# Fogger_Sheild.net
KiCad netlist of a schematic drawn in EAGLE
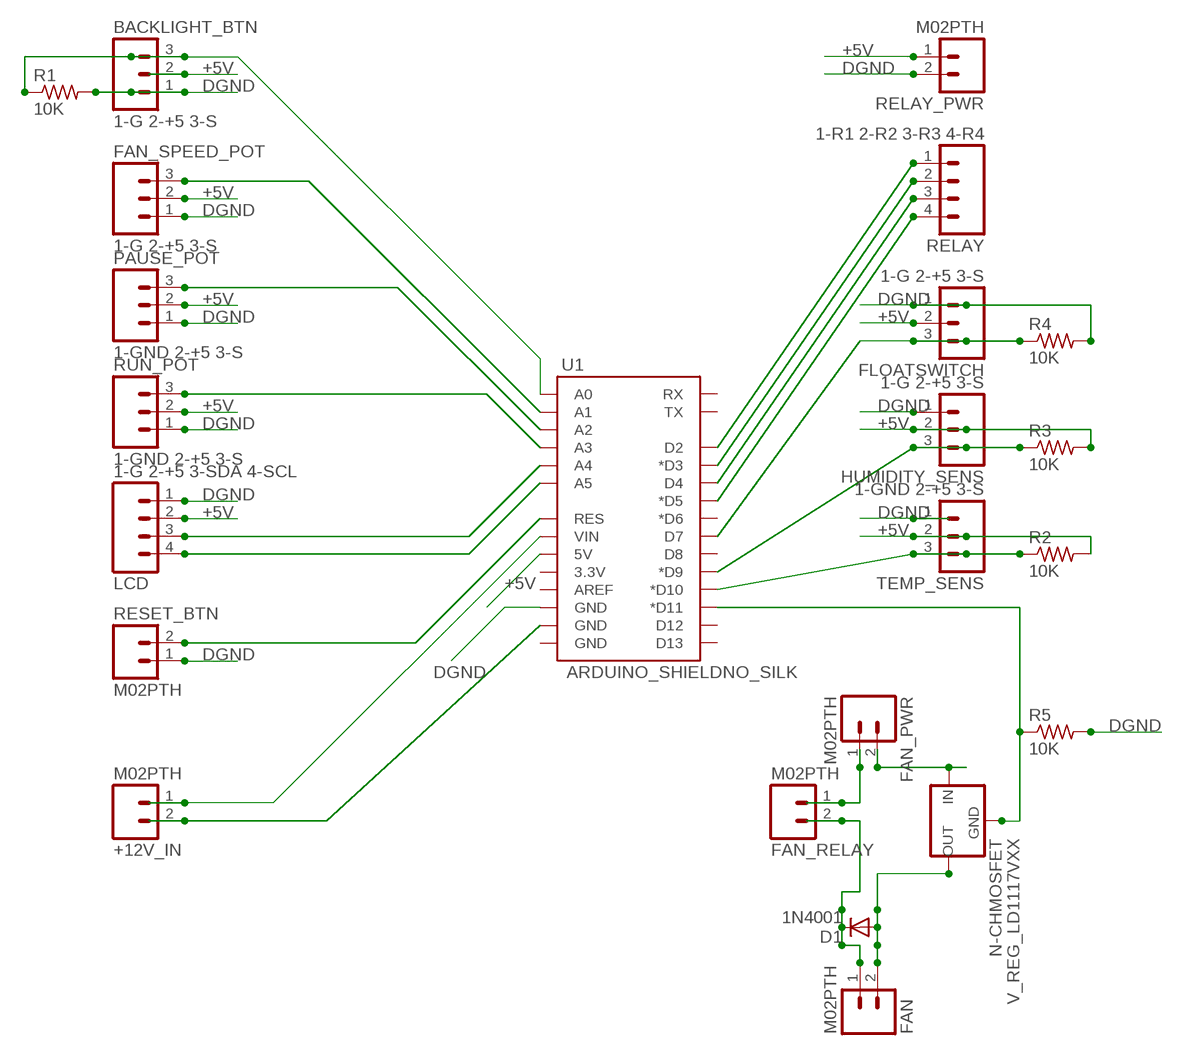
[diagram p0: schematic, sheet 1]

(export (version "E")
  (design (tool "Eeschema 10.0.6"))
  (components
    (comp (ref "+12V_IN")
      (value "M02PTH")
      (footprint "eagle-import:1X02")
      (libsource (lib "eagle-import") (part "M02PTH"))
    )
    (comp (ref "BACKLIGHT_BTN")
      (value "1-G 2-+5 3-S")
      (footprint "eagle-import:1X03_LOCK")
      (libsource (lib "eagle-import") (part "M03LOCK"))
    )
    (comp (ref "D1")
      (value "1N4001")
      (footprint "eagle-import:DIODE-1N4001")
      (libsource (lib "eagle-import") (part "DIODEPTH"))
    )
    (comp (ref "FAN")
      (value "M02PTH")
      (footprint "eagle-import:1X02")
      (libsource (lib "eagle-import") (part "M02PTH"))
    )
    (comp (ref "FAN_PWR")
      (value "M02PTH")
      (footprint "eagle-import:1X02")
      (libsource (lib "eagle-import") (part "M02PTH"))
    )
    (comp (ref "FAN_RELAY")
      (value "M02PTH")
      (footprint "eagle-import:1X02")
      (libsource (lib "eagle-import") (part "M02PTH"))
    )
    (comp (ref "FAN_SPEED_POT")
      (value "1-G 2-+5 3-S")
      (footprint "eagle-import:1X03")
      (libsource (lib "eagle-import") (part "M03PTH"))
    )
    (comp (ref "FLOATSWITCH")
      (value "1-G 2-+5 3-S")
      (footprint "eagle-import:1X03_LOCK")
      (libsource (lib "eagle-import") (part "M03LOCK"))
    )
    (comp (ref "HUMIDITY_SENS")
      (value "1-G 2-+5 3-S")
      (footprint "eagle-import:1X03")
      (libsource (lib "eagle-import") (part "M03PTH"))
    )
    (comp (ref "LCD")
      (value "1-G 2-+5 3-SDA 4-SCL")
      (footprint "eagle-import:1X04")
      (libsource (lib "eagle-import") (part "M04PTH"))
    )
    (comp (ref "N-CHMOSFET")
      (value "V_REG_LD1117VXX")
      (footprint "eagle-import:78XXL")
      (libsource (lib "eagle-import") (part "V_REG_LD1117VXX"))
    )
    (comp (ref "PAUSE_POT")
      (value "1-GND 2-+5 3-S")
      (footprint "eagle-import:1X03_LOCK")
      (libsource (lib "eagle-import") (part "M03LOCK"))
    )
    (comp (ref "R1")
      (value "10K")
      (footprint "eagle-import:0204_5")
      (libsource (lib "eagle-import") (part "R-US_0204/5"))
    )
    (comp (ref "R2")
      (value "10K")
      (footprint "eagle-import:0204V")
      (libsource (lib "eagle-import") (part "R-US_0204/2V"))
    )
    (comp (ref "R3")
      (value "10K")
      (footprint "eagle-import:0204V")
      (libsource (lib "eagle-import") (part "R-US_0204/2V"))
    )
    (comp (ref "R4")
      (value "10K")
      (footprint "eagle-import:0204_5")
      (libsource (lib "eagle-import") (part "R-US_0204/5"))
    )
    (comp (ref "R5")
      (value "10K")
      (footprint "eagle-import:0204V")
      (libsource (lib "eagle-import") (part "R-US_0204/2V"))
    )
    (comp (ref "RELAY")
      (value "1-R1 2-R2 3-R3 4-R4")
      (footprint "eagle-import:1X04")
      (libsource (lib "eagle-import") (part "M04PTH"))
    )
    (comp (ref "RELAY_PWR")
      (value "M02PTH")
      (footprint "eagle-import:1X02")
      (libsource (lib "eagle-import") (part "M02PTH"))
    )
    (comp (ref "RESET_BTN")
      (value "M02PTH")
      (footprint "eagle-import:1X02")
      (libsource (lib "eagle-import") (part "M02PTH"))
    )
    (comp (ref "RUN_POT")
      (value "1-GND 2-+5 3-S")
      (footprint "eagle-import:1X03")
      (libsource (lib "eagle-import") (part "M03PTH"))
    )
    (comp (ref "TEMP_SENS")
      (value "1-GND 2-+5 3-S")
      (footprint "eagle-import:1X03_LOCK")
      (libsource (lib "eagle-import") (part "M03LOCK"))
    )
    (comp (ref "U1")
      (value "ARDUINO_SHIELDNO_SILK")
      (footprint "eagle-import:DUEMILANOVE_VIAS")
      (libsource (lib "eagle-import") (part "ARDUINO_SHIELDNO_SILK"))
    )
  )
  (nets
    (net (code "1") (name "/+5V") (class "Default")
      (node (ref "BACKLIGHT_BTN") (pin "2") (pinfunction "2_2") (pintype "passive"))
      (node (ref "FAN_SPEED_POT") (pin "2") (pinfunction "2_2") (pintype "passive"))
      (node (ref "FLOATSWITCH") (pin "2") (pinfunction "2_2") (pintype "passive"))
      (node (ref "HUMIDITY_SENS") (pin "2") (pinfunction "2_2") (pintype "passive"))
      (node (ref "LCD") (pin "2") (pinfunction "2_2") (pintype "passive"))
      (node (ref "PAUSE_POT") (pin "2") (pinfunction "2_2") (pintype "passive"))
      (node (ref "R2") (pin "2") (pinfunction "2_2") (pintype "passive"))
      (node (ref "R3") (pin "2") (pinfunction "2_2") (pintype "passive"))
      (node (ref "RELAY_PWR") (pin "1") (pinfunction "1_1") (pintype "passive"))
      (node (ref "RUN_POT") (pin "2") (pinfunction "2_2") (pintype "passive"))
      (node (ref "TEMP_SENS") (pin "2") (pinfunction "2_2") (pintype "passive"))
      (node (ref "U1") (pin "5V") (pinfunction "5V_5V") (pintype "bidirectional"))
    )
    (net (code "2") (name "/DGND") (class "Default")
      (node (ref "BACKLIGHT_BTN") (pin "1") (pinfunction "1_1") (pintype "passive"))
      (node (ref "FAN_SPEED_POT") (pin "1") (pinfunction "1_1") (pintype "passive"))
      (node (ref "FLOATSWITCH") (pin "1") (pinfunction "1_1") (pintype "passive"))
      (node (ref "HUMIDITY_SENS") (pin "1") (pinfunction "1_1") (pintype "passive"))
      (node (ref "LCD") (pin "1") (pinfunction "1_1") (pintype "passive"))
      (node (ref "PAUSE_POT") (pin "1") (pinfunction "1_1") (pintype "passive"))
      (node (ref "R1") (pin "2") (pinfunction "2_2") (pintype "passive"))
      (node (ref "R4") (pin "2") (pinfunction "2_2") (pintype "passive"))
      (node (ref "R5") (pin "2") (pinfunction "2_2") (pintype "passive"))
      (node (ref "RELAY_PWR") (pin "2") (pinfunction "2_2") (pintype "passive"))
      (node (ref "RESET_BTN") (pin "1") (pinfunction "1_1") (pintype "passive"))
      (node (ref "RUN_POT") (pin "1") (pinfunction "1_1") (pintype "passive"))
      (node (ref "TEMP_SENS") (pin "1") (pinfunction "1_1") (pintype "passive"))
      (node (ref "U1") (pin "GND@2") (pinfunction "GND_GND@2") (pintype "bidirectional"))
    )
    (net (code "3") (name "Net-(+12V_IN-Pad1)") (class "Default")
      (node (ref "+12V_IN") (pin "1") (pinfunction "1_1") (pintype "passive"))
      (node (ref "U1") (pin "VIN") (pinfunction "VIN_VIN") (pintype "bidirectional"))
    )
    (net (code "4") (name "Net-(+12V_IN-Pad2)") (class "Default")
      (node (ref "+12V_IN") (pin "2") (pinfunction "2_2") (pintype "passive"))
      (node (ref "U1") (pin "GND@1") (pinfunction "GND_GND@1") (pintype "bidirectional"))
    )
    (net (code "5") (name "Net-(BACKLIGHT_BTN-Pad3)") (class "Default")
      (node (ref "BACKLIGHT_BTN") (pin "3") (pinfunction "3_3") (pintype "passive"))
      (node (ref "R1") (pin "1") (pinfunction "1_1") (pintype "passive"))
      (node (ref "U1") (pin "A0") (pinfunction "A0_A0") (pintype "bidirectional"))
    )
    (net (code "6") (name "Net-(D1-PadC)") (class "Default")
      (node (ref "D1") (pin "C") (pinfunction "C_C") (pintype "passive"))
      (node (ref "FAN") (pin "1") (pinfunction "1_1") (pintype "passive"))
      (node (ref "FAN_RELAY") (pin "2") (pinfunction "2_2") (pintype "passive"))
    )
    (net (code "7") (name "Net-(FAN_PWR-Pad1)") (class "Default")
      (node (ref "FAN_PWR") (pin "1") (pinfunction "1_1") (pintype "passive"))
      (node (ref "FAN_RELAY") (pin "1") (pinfunction "1_1") (pintype "passive"))
    )
    (net (code "8") (name "Net-(FAN_SPEED_POT-Pad3)") (class "Default")
      (node (ref "FAN_SPEED_POT") (pin "3") (pinfunction "3_3") (pintype "passive"))
      (node (ref "U1") (pin "A1") (pinfunction "A1_A1") (pintype "bidirectional"))
    )
    (net (code "9") (name "Net-(FLOATSWITCH-Pad3)") (class "Default")
      (node (ref "FLOATSWITCH") (pin "3") (pinfunction "3_3") (pintype "passive"))
      (node (ref "R4") (pin "1") (pinfunction "1_1") (pintype "passive"))
      (node (ref "U1") (pin "D7") (pinfunction "D7_D7") (pintype "bidirectional"))
    )
    (net (code "10") (name "Net-(LCD-Pad3)") (class "Default")
      (node (ref "LCD") (pin "3") (pinfunction "3_3") (pintype "passive"))
      (node (ref "U1") (pin "A4") (pinfunction "A4_A4") (pintype "bidirectional"))
    )
    (net (code "11") (name "Net-(LCD-Pad4)") (class "Default")
      (node (ref "LCD") (pin "4") (pinfunction "4_4") (pintype "passive"))
      (node (ref "U1") (pin "A5") (pinfunction "A5_A5") (pintype "bidirectional"))
    )
    (net (code "12") (name "Net-(N-CHMOSFET-GND)") (class "Default")
      (node (ref "N-CHMOSFET") (pin "IN") (pinfunction "GND_IN") (pintype "input"))
      (node (ref "R5") (pin "1") (pinfunction "1_1") (pintype "passive"))
      (node (ref "U1") (pin "D11") (pinfunction "*D11_D11") (pintype "bidirectional"))
    )
    (net (code "13") (name "Net-(N-CHMOSFET-IN)") (class "Default")
      (node (ref "FAN_PWR") (pin "2") (pinfunction "2_2") (pintype "passive"))
      (node (ref "N-CHMOSFET") (pin "OUT") (pinfunction "IN_OUT") (pintype "input"))
    )
    (net (code "14") (name "Net-(N-CHMOSFET-OUT)") (class "Default")
      (node (ref "D1") (pin "A") (pinfunction "A_A") (pintype "passive"))
      (node (ref "FAN") (pin "2") (pinfunction "2_2") (pintype "passive"))
      (node (ref "N-CHMOSFET") (pin "GND") (pinfunction "OUT_GND") (pintype "output"))
    )
    (net (code "15") (name "Net-(PAUSE_POT-Pad3)") (class "Default")
      (node (ref "PAUSE_POT") (pin "3") (pinfunction "3_3") (pintype "passive"))
      (node (ref "U1") (pin "A2") (pinfunction "A2_A2") (pintype "bidirectional"))
    )
    (net (code "16") (name "Net-(RELAY-Pad1)") (class "Default")
      (node (ref "RELAY") (pin "1") (pinfunction "1_1") (pintype "passive"))
      (node (ref "U1") (pin "D2") (pinfunction "D2_D2") (pintype "bidirectional"))
    )
    (net (code "17") (name "Net-(RELAY-Pad3)") (class "Default")
      (node (ref "RELAY") (pin "3") (pinfunction "3_3") (pintype "passive"))
      (node (ref "U1") (pin "D4") (pinfunction "D4_D4") (pintype "bidirectional"))
    )
    (net (code "18") (name "Net-(RESET_BTN-Pad2)") (class "Default")
      (node (ref "RESET_BTN") (pin "2") (pinfunction "2_2") (pintype "passive"))
      (node (ref "U1") (pin "RES") (pinfunction "RES_RES") (pintype "bidirectional"))
    )
    (net (code "19") (name "Net-(RUN_POT-Pad3)") (class "Default")
      (node (ref "RUN_POT") (pin "3") (pinfunction "3_3") (pintype "passive"))
      (node (ref "U1") (pin "A3") (pinfunction "A3_A3") (pintype "bidirectional"))
    )
    (net (code "20") (name "Net-(U1-*D3)") (class "Default")
      (node (ref "RELAY") (pin "2") (pinfunction "2_2") (pintype "passive"))
      (node (ref "U1") (pin "D3") (pinfunction "*D3_D3") (pintype "bidirectional"))
    )
    (net (code "21") (name "Net-(U1-*D5)") (class "Default")
      (node (ref "RELAY") (pin "4") (pinfunction "4_4") (pintype "passive"))
      (node (ref "U1") (pin "D5") (pinfunction "*D5_D5") (pintype "bidirectional"))
    )
    (net (code "22") (name "Net-(U1-*D9)") (class "Default")
      (node (ref "HUMIDITY_SENS") (pin "3") (pinfunction "3_3") (pintype "passive"))
      (node (ref "R3") (pin "1") (pinfunction "1_1") (pintype "passive"))
      (node (ref "U1") (pin "D9") (pinfunction "*D9_D9") (pintype "bidirectional"))
    )
    (net (code "23") (name "Net-(U1-*D10)") (class "Default")
      (node (ref "R2") (pin "1") (pinfunction "1_1") (pintype "passive"))
      (node (ref "TEMP_SENS") (pin "3") (pinfunction "3_3") (pintype "passive"))
      (node (ref "U1") (pin "D10") (pinfunction "*D10_D10") (pintype "bidirectional"))
    )
    (net (code "24") (name "unconnected-(U1-*D6-PadD6)") (class "Default")
      (node (ref "U1") (pin "D6") (pinfunction "*D6_D6") (pintype "bidirectional"))
    )
    (net (code "25") (name "unconnected-(U1-GND-PadGND@0)") (class "Default")
      (node (ref "U1") (pin "GND@0") (pinfunction "GND_GND@0") (pintype "bidirectional"))
    )
    (net (code "26") (name "unconnected-(U1-Pad3.3V)") (class "Default")
      (node (ref "U1") (pin "3.3V") (pinfunction "3.3V_3.3V") (pintype "bidirectional"))
    )
    (net (code "27") (name "unconnected-(U1-PadAREF)") (class "Default")
      (node (ref "U1") (pin "AREF") (pinfunction "AREF_AREF") (pintype "bidirectional"))
    )
    (net (code "28") (name "unconnected-(U1-PadD8)") (class "Default")
      (node (ref "U1") (pin "D8") (pinfunction "D8_D8") (pintype "bidirectional"))
    )
    (net (code "29") (name "unconnected-(U1-PadD12)") (class "Default")
      (node (ref "U1") (pin "D12") (pinfunction "D12_D12") (pintype "bidirectional"))
    )
    (net (code "30") (name "unconnected-(U1-PadD13)") (class "Default")
      (node (ref "U1") (pin "D13") (pinfunction "D13_D13") (pintype "bidirectional"))
    )
    (net (code "31") (name "unconnected-(U1-PadRX)") (class "Default")
      (node (ref "U1") (pin "RX") (pinfunction "RX_RX") (pintype "bidirectional"))
    )
    (net (code "32") (name "unconnected-(U1-PadTX)") (class "Default")
      (node (ref "U1") (pin "TX") (pinfunction "TX_TX") (pintype "bidirectional"))
    )
  )
)
